# microcontroller.net
KiCad netlist of a schematic drawn in Altium Designer
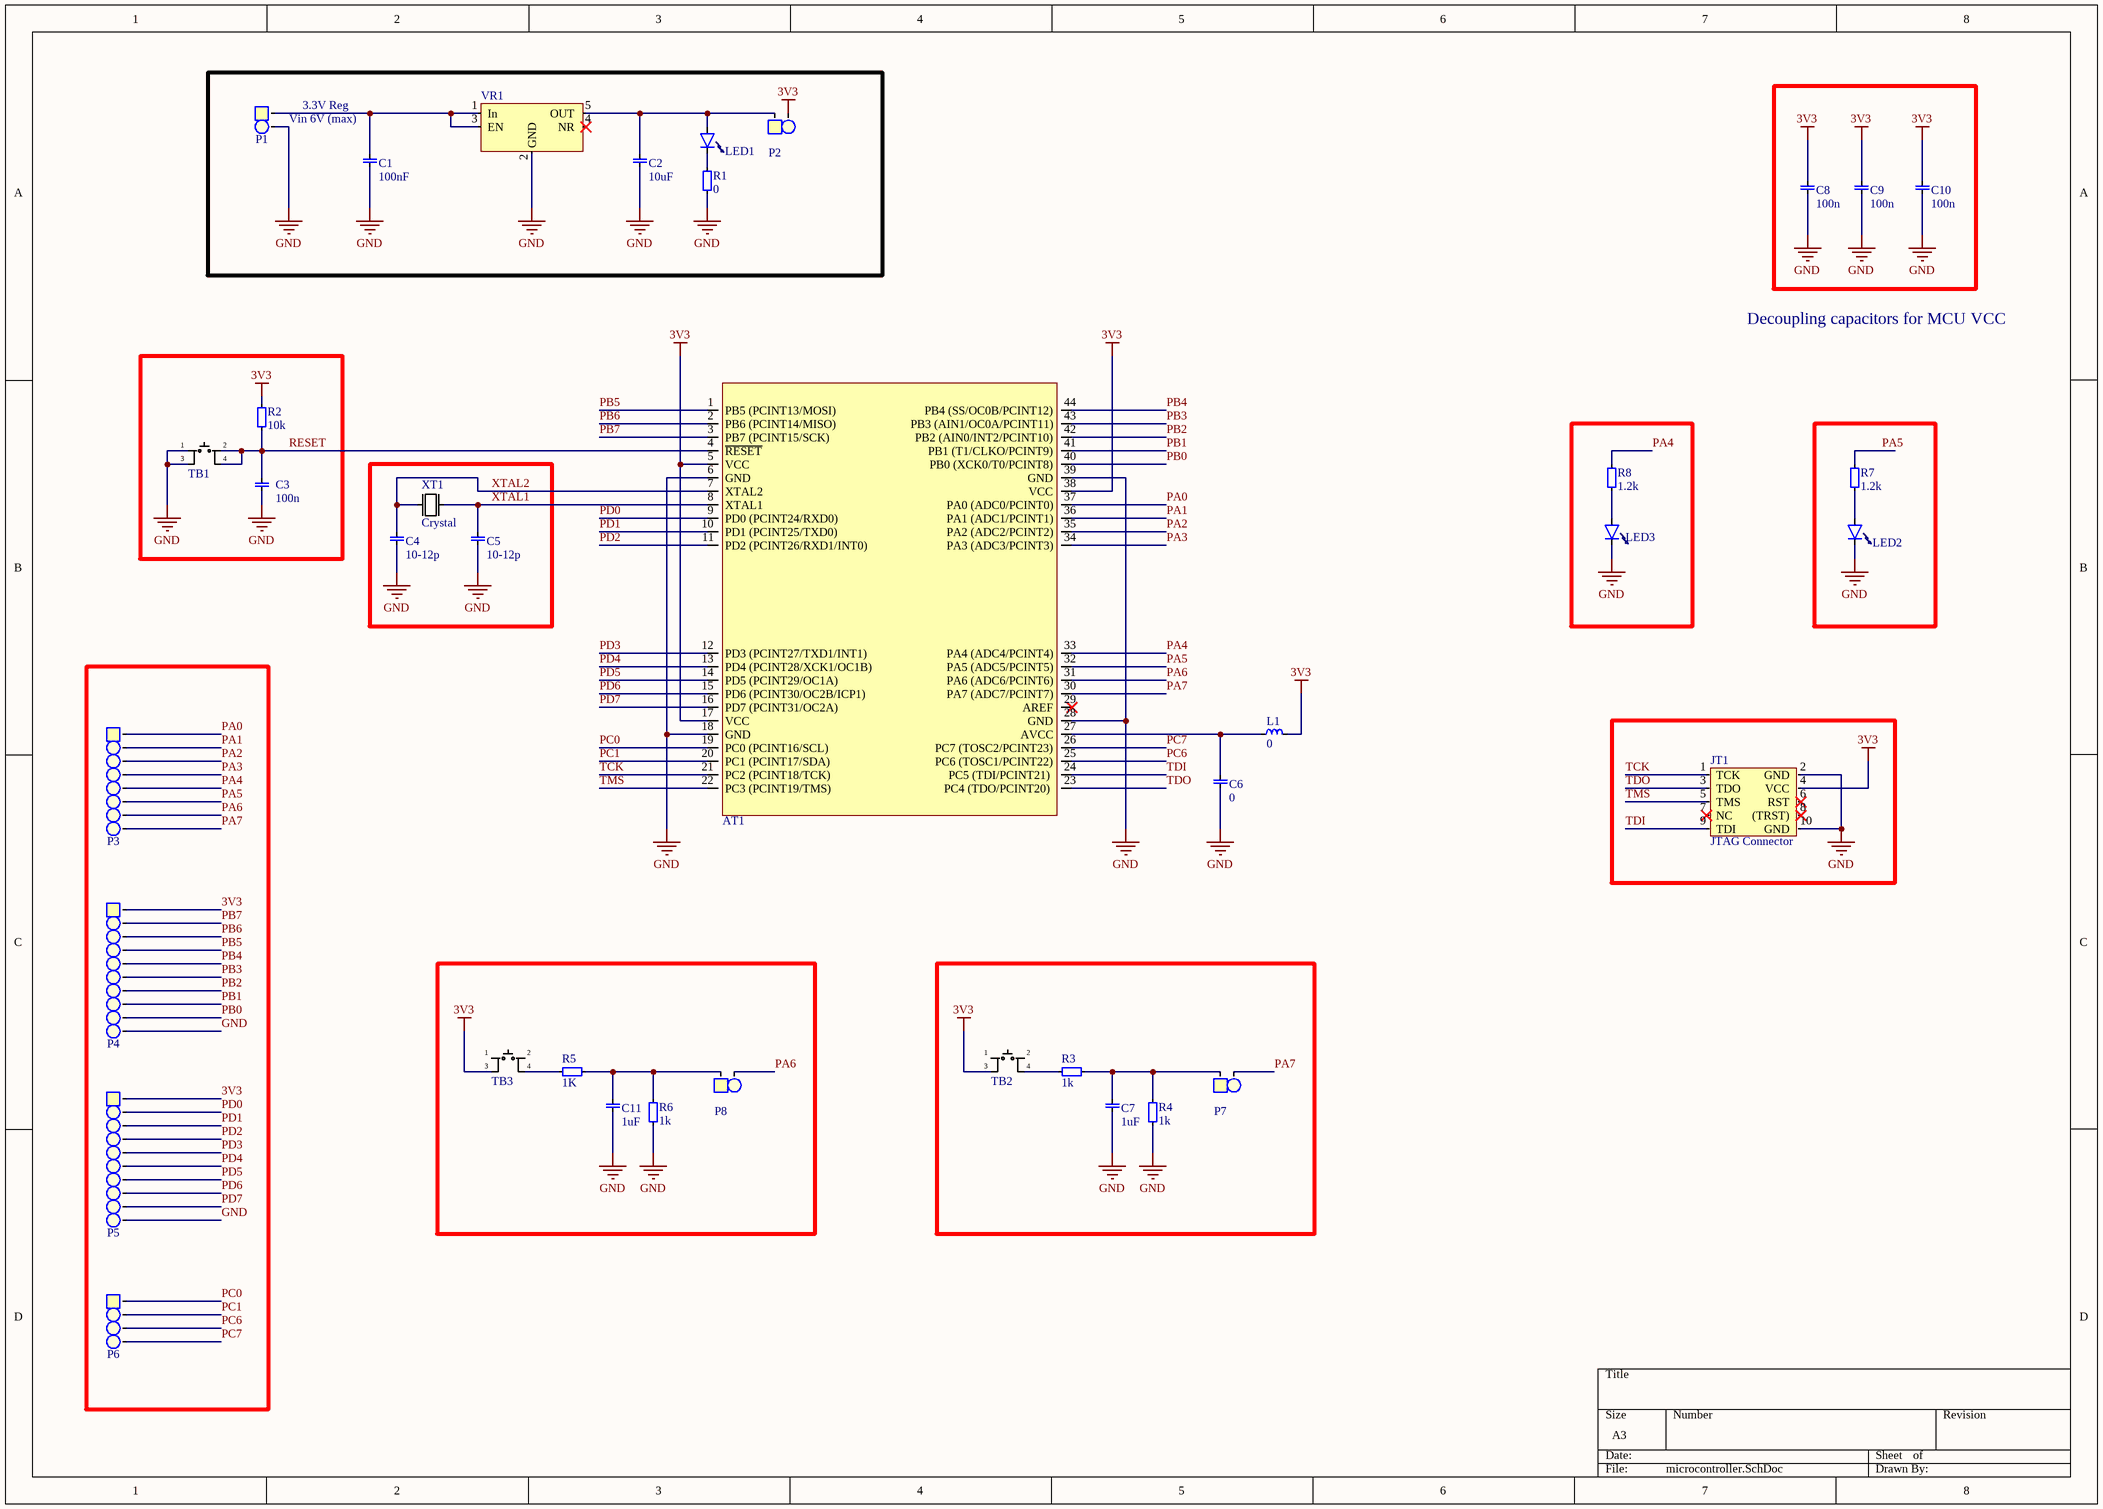
[diagram p0: microcontroller.SchDoc]

(export (version "E")
  (design (tool "Eeschema 10.0.6"))
  (components
    (comp (ref "AT1")
      (value "ATmega644PA")
      (footprint "TQFP-44")
      (description "ATmega644PA - Small but big and PicoPower")
      (libsource (lib "eitp15_lab1_lib") (part "ATmega644PA"))
    )
    (comp (ref "C1")
      (value "100nF")
      (footprint "1206, capasitor")
      (fields (field (name "Comment") "1206, capacitor"))
      (libsource (lib "eitp15_lab1_lib") (part "1206, capacitor"))
    )
    (comp (ref "C2")
      (value "10uF")
      (footprint "1206, capasitor")
      (fields (field (name "Comment") "1206, capacitor"))
      (libsource (lib "eitp15_lab1_lib") (part "1206, capacitor"))
    )
    (comp (ref "C3")
      (value "100n")
      (footprint "1206, capasitor")
      (fields (field (name "Comment") "1206, capacitor"))
      (libsource (lib "eitp15_lab1_lib") (part "1206, capacitor"))
    )
    (comp (ref "C4")
      (value "10-12p")
      (footprint "1206, capasitor")
      (fields (field (name "Comment") "1206, capacitor"))
      (libsource (lib "eitp15_lab1_lib") (part "1206, capacitor"))
    )
    (comp (ref "C5")
      (value "10-12p")
      (footprint "1206, capasitor")
      (fields (field (name "Comment") "1206, capacitor"))
      (libsource (lib "eitp15_lab1_lib") (part "1206, capacitor"))
    )
    (comp (ref "C6")
      (value "0")
      (footprint "1206, capasitor")
      (fields (field (name "Comment") "1206, capacitor"))
      (libsource (lib "eitp15_lab1_lib") (part "1206, capacitor"))
    )
    (comp (ref "C7")
      (value "1uF")
      (footprint "1206, capasitor")
      (fields (field (name "Comment") "1206, capacitor"))
      (libsource (lib "eitp15_lab1_lib") (part "1206, capacitor"))
    )
    (comp (ref "C8")
      (value "100n")
      (footprint "1206, capasitor")
      (fields (field (name "Comment") "1206, capacitor"))
      (libsource (lib "eitp15_lab1_lib") (part "1206, capacitor"))
    )
    (comp (ref "C9")
      (value "100n")
      (footprint "1206, capasitor")
      (fields (field (name "Comment") "1206, capacitor"))
      (libsource (lib "eitp15_lab1_lib") (part "1206, capacitor"))
    )
    (comp (ref "C10")
      (value "100n")
      (footprint "1206, capasitor")
      (fields (field (name "Comment") "1206, capacitor"))
      (libsource (lib "eitp15_lab1_lib") (part "1206, capacitor"))
    )
    (comp (ref "C11")
      (value "1uF")
      (footprint "1206, capasitor")
      (fields (field (name "Comment") "1206, capacitor"))
      (libsource (lib "eitp15_lab1_lib") (part "1206, capacitor"))
    )
    (comp (ref "JT1")
      (value "JTAG Connector")
      (footprint "Atmel_JTAG")
      (description "Atmel JTAG Connector")
      (libsource (lib "eitp15_lab1_lib") (part "Atmel JTAG"))
    )
    (comp (ref "L1")
      (value "0")
      (footprint "1812, coil")
      (fields (field (name "Comment") "Coil"))
      (libsource (lib "eitp15_lab1_lib") (part "Coil"))
    )
    (comp (ref "LED1")
      (value "0805, LED")
      (footprint "0805_led")
      (libsource (lib "eitp15_lab1_lib") (part "0805, LED"))
    )
    (comp (ref "LED2")
      (value "0805, LED")
      (footprint "0805_led")
      (libsource (lib "eitp15_lab1_lib") (part "0805, LED"))
    )
    (comp (ref "LED3")
      (value "0805, LED")
      (footprint "0805_led")
      (libsource (lib "eitp15_lab1_lib") (part "0805, LED"))
    )
    (comp (ref "P1")
      (value "1x2 Pin Header")
      (footprint "1x2HEADER")
      (description "2.54 mm, TH")
      (libsource (lib "") (part "1x2 Pin Header_1"))
    )
    (comp (ref "P2")
      (value "1x2 Pin Header")
      (footprint "1x2HEADER")
      (description "2.54 mm, TH")
      (libsource (lib "eitp15_lab1_lib") (part "1x2 Pin Header"))
    )
    (comp (ref "P3")
      (value "1x8 Pin Header")
      (footprint "1x8HEADER")
      (description "2.54 mm, TH")
      (libsource (lib "eitp15_lab1_lib") (part "1x8 Pin Header"))
    )
    (comp (ref "P4")
      (value "1x10 Pin Header")
      (footprint "1x10HEADER")
      (description "2.54 mm, TH")
      (libsource (lib "eitp15_lab1_lib") (part "1x10 Pin Header"))
    )
    (comp (ref "P5")
      (value "1x10 Pin Header")
      (footprint "1x10HEADER")
      (description "2.54 mm, TH")
      (libsource (lib "eitp15_lab1_lib") (part "1x10 Pin Header"))
    )
    (comp (ref "P6")
      (value "1x4 Pin Header")
      (footprint "1x4HEADER")
      (description "2.54 mm, TH")
      (libsource (lib "eitp15_lab1_lib") (part "1x4 Pin Header"))
    )
    (comp (ref "P7")
      (value "1x2 Pin Header")
      (footprint "1x2HEADER")
      (description "2.54 mm, TH")
      (libsource (lib "eitp15_lab1_lib") (part "1x2 Pin Header"))
    )
    (comp (ref "P8")
      (value "1x2 Pin Header")
      (footprint "1x2HEADER")
      (description "2.54 mm, TH")
      (libsource (lib "eitp15_lab1_lib") (part "1x2 Pin Header"))
    )
    (comp (ref "R1")
      (value "0")
      (footprint "1206")
      (description "Resistor")
      (fields (field (name "Comment") "1206, resistor"))
      (libsource (lib "eitp15_lab1_lib") (part "1206, resistor"))
    )
    (comp (ref "R2")
      (value "10k")
      (footprint "1206")
      (description "Resistor")
      (fields (field (name "Comment") "1206, resistor"))
      (libsource (lib "eitp15_lab1_lib") (part "1206, resistor"))
    )
    (comp (ref "R3")
      (value "1k")
      (footprint "1206")
      (description "Resistor")
      (fields (field (name "Comment") "1206, resistor"))
      (libsource (lib "eitp15_lab1_lib") (part "1206, resistor"))
    )
    (comp (ref "R4")
      (value "1k")
      (footprint "1206")
      (description "Resistor")
      (fields (field (name "Comment") "1206, resistor"))
      (libsource (lib "eitp15_lab1_lib") (part "1206, resistor"))
    )
    (comp (ref "R5")
      (value "1K")
      (footprint "1206")
      (description "Resistor")
      (fields (field (name "Comment") "1206, resistor"))
      (libsource (lib "eitp15_lab1_lib") (part "1206, resistor"))
    )
    (comp (ref "R6")
      (value "1k")
      (footprint "1206")
      (description "Resistor")
      (fields (field (name "Comment") "1206, resistor"))
      (libsource (lib "eitp15_lab1_lib") (part "1206, resistor"))
    )
    (comp (ref "R7")
      (value "1.2k")
      (footprint "1206")
      (description "Resistor")
      (fields (field (name "Comment") "1206, resistor"))
      (libsource (lib "eitp15_lab1_lib") (part "1206, resistor"))
    )
    (comp (ref "R8")
      (value "1.2k")
      (footprint "1206")
      (description "Resistor")
      (fields (field (name "Comment") "1206, resistor"))
      (libsource (lib "eitp15_lab1_lib") (part "1206, resistor"))
    )
    (comp (ref "TB1")
      (value "Tactile Button")
      (footprint "Button smd")
      (description "Tactile Switch Small Low")
      (libsource (lib "eitp15_lab1_lib") (part "Button SMD"))
    )
    (comp (ref "TB2")
      (value "Tactile Button")
      (footprint "Button smd")
      (description "Tactile Switch Small Low")
      (libsource (lib "eitp15_lab1_lib") (part "Button SMD"))
    )
    (comp (ref "TB3")
      (value "Tactile Button")
      (footprint "Button smd")
      (description "Tactile Switch Small Low")
      (libsource (lib "eitp15_lab1_lib") (part "Button SMD"))
    )
    (comp (ref "VR1")
      (value "3.3V Reg")
      (footprint "SOT23-5")
      (description "3.3V Reg, Ultra-Low Noise, 200 mA")
      (fields (field (name "INPUT VOLTAGE") "Vin 6V (max)"))
      (libsource (lib "eitp15_lab1_lib") (part "TPS79333DBR"))
    )
    (comp (ref "XT1")
      (value "Crystal")
      (footprint "XTAL_SMD_LP")
      (description "16 MHz, SMD, 5mm x 3,2mm, 30 ppm")
      (fields (field (name "Comment") "XTAL TXC 7A"))
      (libsource (lib "eitp15_lab1_lib") (part "XTAL TXC 7A"))
    )
  )
  (nets
    (net (code "1") (name "/PA0") (class "Default")
      (node (ref "AT1") (pin "37") (pinfunction "PA0_(ADC0/PCINT0)_37") (pintype "passive"))
      (node (ref "P3") (pin "1") (pinfunction "1_1") (pintype "passive"))
    )
    (net (code "2") (name "/PA1") (class "Default")
      (node (ref "AT1") (pin "36") (pinfunction "PA1_(ADC1/PCINT1)_36") (pintype "passive"))
      (node (ref "P3") (pin "2") (pinfunction "2_2") (pintype "passive"))
    )
    (net (code "3") (name "/PA2") (class "Default")
      (node (ref "AT1") (pin "35") (pinfunction "PA2_(ADC2/PCINT2)_35") (pintype "passive"))
      (node (ref "P3") (pin "3") (pinfunction "3_3") (pintype "passive"))
    )
    (net (code "4") (name "/PA3") (class "Default")
      (node (ref "AT1") (pin "34") (pinfunction "PA3_(ADC3/PCINT3)_34") (pintype "passive"))
      (node (ref "P3") (pin "4") (pinfunction "4_4") (pintype "passive"))
    )
    (net (code "5") (name "/PA4") (class "Default")
      (node (ref "AT1") (pin "33") (pinfunction "PA4_(ADC4/PCINT4)_33") (pintype "passive"))
      (node (ref "P3") (pin "5") (pinfunction "5_5") (pintype "passive"))
      (node (ref "R8") (pin "0") (pinfunction "0_0") (pintype "passive"))
    )
    (net (code "6") (name "/PA5") (class "Default")
      (node (ref "AT1") (pin "32") (pinfunction "PA5_(ADC5/PCINT5)_32") (pintype "passive"))
      (node (ref "P3") (pin "6") (pinfunction "6_6") (pintype "passive"))
      (node (ref "R7") (pin "0") (pinfunction "0_0") (pintype "passive"))
    )
    (net (code "7") (name "/PA6") (class "Default")
      (node (ref "AT1") (pin "31") (pinfunction "PA6_(ADC6/PCINT6)_31") (pintype "passive"))
      (node (ref "P3") (pin "7") (pinfunction "7_7") (pintype "passive"))
      (node (ref "P8") (pin "2") (pinfunction "2_2") (pintype "passive"))
    )
    (net (code "8") (name "/PA7") (class "Default")
      (node (ref "AT1") (pin "30") (pinfunction "PA7_(ADC7/PCINT7)_30") (pintype "passive"))
      (node (ref "P3") (pin "8") (pinfunction "8_8") (pintype "passive"))
      (node (ref "P7") (pin "2") (pinfunction "2_2") (pintype "passive"))
    )
    (net (code "9") (name "/PB0") (class "Default")
      (node (ref "AT1") (pin "40") (pinfunction "PB0_(XCK0/T0/PCINT8)_40") (pintype "passive"))
      (node (ref "P4") (pin "9") (pinfunction "9_9") (pintype "passive"))
    )
    (net (code "10") (name "/PB1") (class "Default")
      (node (ref "AT1") (pin "41") (pinfunction "PB1_(T1/CLKO/PCINT9)_41") (pintype "passive"))
      (node (ref "P4") (pin "8") (pinfunction "8_8") (pintype "passive"))
    )
    (net (code "11") (name "/PB2") (class "Default")
      (node (ref "AT1") (pin "42") (pinfunction "PB2_(AIN0/INT2/PCINT10)_42") (pintype "passive"))
      (node (ref "P4") (pin "7") (pinfunction "7_7") (pintype "passive"))
    )
    (net (code "12") (name "/PB3") (class "Default")
      (node (ref "AT1") (pin "43") (pinfunction "PB3_(AIN1/OC0A/PCINT11)_43") (pintype "passive"))
      (node (ref "P4") (pin "6") (pinfunction "6_6") (pintype "passive"))
    )
    (net (code "13") (name "/PB4") (class "Default")
      (node (ref "AT1") (pin "44") (pinfunction "PB4_(SS/OC0B/PCINT12)_44") (pintype "passive"))
      (node (ref "P4") (pin "5") (pinfunction "5_5") (pintype "passive"))
    )
    (net (code "14") (name "/PB5") (class "Default")
      (node (ref "AT1") (pin "1") (pinfunction "PB5_(PCINT13/MOSI)_1") (pintype "passive"))
      (node (ref "P4") (pin "4") (pinfunction "4_4") (pintype "passive"))
    )
    (net (code "15") (name "/PB6") (class "Default")
      (node (ref "AT1") (pin "2") (pinfunction "PB6_(PCINT14/MISO)_2") (pintype "passive"))
      (node (ref "P4") (pin "3") (pinfunction "3_3") (pintype "passive"))
    )
    (net (code "16") (name "/PB7") (class "Default")
      (node (ref "AT1") (pin "3") (pinfunction "PB7_(PCINT15/SCK)_3") (pintype "passive"))
      (node (ref "P4") (pin "2") (pinfunction "2_2") (pintype "passive"))
    )
    (net (code "17") (name "/PC0") (class "Default")
      (node (ref "AT1") (pin "19") (pinfunction "PC0_(PCINT16/SCL)_19") (pintype "passive"))
      (node (ref "P6") (pin "1") (pinfunction "1_1") (pintype "passive"))
    )
    (net (code "18") (name "/PC1") (class "Default")
      (node (ref "AT1") (pin "20") (pinfunction "PC1_(PCINT17/SDA)_20") (pintype "passive"))
      (node (ref "P6") (pin "2") (pinfunction "2_2") (pintype "passive"))
    )
    (net (code "19") (name "/PC6") (class "Default")
      (node (ref "AT1") (pin "25") (pinfunction "PC6_(TOSC1/PCINT22)_25") (pintype "passive"))
      (node (ref "P6") (pin "3") (pinfunction "3_3") (pintype "passive"))
    )
    (net (code "20") (name "/PC7") (class "Default")
      (node (ref "AT1") (pin "26") (pinfunction "PC7_(TOSC2/PCINT23)_26") (pintype "passive"))
      (node (ref "P6") (pin "4") (pinfunction "4_4") (pintype "passive"))
    )
    (net (code "21") (name "/PD0") (class "Default")
      (node (ref "AT1") (pin "9") (pinfunction "PD0_(PCINT24/RXD0)_9") (pintype "passive"))
      (node (ref "P5") (pin "2") (pinfunction "2_2") (pintype "passive"))
    )
    (net (code "22") (name "/PD1") (class "Default")
      (node (ref "AT1") (pin "10") (pinfunction "PD1_(PCINT25/TXD0)_10") (pintype "passive"))
      (node (ref "P5") (pin "3") (pinfunction "3_3") (pintype "passive"))
    )
    (net (code "23") (name "/PD2") (class "Default")
      (node (ref "AT1") (pin "11") (pinfunction "PD2_(PCINT26/RXD1/INT0)_11") (pintype "passive"))
      (node (ref "P5") (pin "4") (pinfunction "4_4") (pintype "passive"))
    )
    (net (code "24") (name "/PD3") (class "Default")
      (node (ref "AT1") (pin "12") (pinfunction "PD3_(PCINT27/TXD1/INT1)_12") (pintype "passive"))
      (node (ref "P5") (pin "5") (pinfunction "5_5") (pintype "passive"))
    )
    (net (code "25") (name "/PD4") (class "Default")
      (node (ref "AT1") (pin "13") (pinfunction "PD4_(PCINT28/XCK1/OC1B)_13") (pintype "passive"))
      (node (ref "P5") (pin "6") (pinfunction "6_6") (pintype "passive"))
    )
    (net (code "26") (name "/PD5") (class "Default")
      (node (ref "AT1") (pin "14") (pinfunction "PD5_(PCINT29/OC1A)_14") (pintype "passive"))
      (node (ref "P5") (pin "7") (pinfunction "7_7") (pintype "passive"))
    )
    (net (code "27") (name "/PD6") (class "Default")
      (node (ref "AT1") (pin "15") (pinfunction "PD6_(PCINT30/OC2B/ICP1)_15") (pintype "passive"))
      (node (ref "P5") (pin "8") (pinfunction "8_8") (pintype "passive"))
    )
    (net (code "28") (name "/PD7") (class "Default")
      (node (ref "AT1") (pin "16") (pinfunction "PD7_(PCINT31/OC2A)_16") (pintype "passive"))
      (node (ref "P5") (pin "9") (pinfunction "9_9") (pintype "passive"))
    )
    (net (code "29") (name "/RESET") (class "Default")
      (node (ref "AT1") (pin "4") (pinfunction "~{RESET}_4") (pintype "passive"))
      (node (ref "C3") (pin "1") (pinfunction "1_1") (pintype "passive"))
      (node (ref "R2") (pin "1") (pinfunction "1_1") (pintype "passive"))
      (node (ref "TB1") (pin "2") (pinfunction "2_2") (pintype "passive"))
      (node (ref "TB1") (pin "4") (pinfunction "4_4") (pintype "passive"))
    )
    (net (code "30") (name "/TCK") (class "Default")
      (node (ref "AT1") (pin "21") (pinfunction "PC2_(PCINT18/TCK)_21") (pintype "passive"))
      (node (ref "JT1") (pin "1") (pinfunction "TCK_1") (pintype "passive"))
    )
    (net (code "31") (name "/TDI") (class "Default")
      (node (ref "AT1") (pin "24") (pinfunction "PC5_(TDI/PCINT21)_24") (pintype "passive"))
      (node (ref "JT1") (pin "9") (pinfunction "TDI_9") (pintype "passive"))
    )
    (net (code "32") (name "/TDO") (class "Default")
      (node (ref "AT1") (pin "23") (pinfunction "PC4_(TDO/PCINT20)_23") (pintype "passive"))
      (node (ref "JT1") (pin "3") (pinfunction "TDO_3") (pintype "passive"))
    )
    (net (code "33") (name "/TMS") (class "Default")
      (node (ref "AT1") (pin "22") (pinfunction "PC3_(PCINT19/TMS)_22") (pintype "passive"))
      (node (ref "JT1") (pin "5") (pinfunction "TMS_5") (pintype "passive"))
    )
    (net (code "34") (name "/XTAL1") (class "Default")
      (node (ref "AT1") (pin "8") (pinfunction "XTAL1_8") (pintype "passive"))
      (node (ref "C5") (pin "1") (pinfunction "1_1") (pintype "passive"))
      (node (ref "XT1") (pin "2") (pinfunction "2_2") (pintype "passive"))
    )
    (net (code "35") (name "/XTAL2") (class "Default")
      (node (ref "AT1") (pin "7") (pinfunction "XTAL2_7") (pintype "passive"))
      (node (ref "C4") (pin "1") (pinfunction "1_1") (pintype "passive"))
      (node (ref "XT1") (pin "1") (pinfunction "1_1") (pintype "passive"))
    )
    (net (code "36") (name "3V3") (class "Default")
      (node (ref "AT1") (pin "17") (pinfunction "VCC_17") (pintype "passive"))
      (node (ref "AT1") (pin "38") (pinfunction "VCC_38") (pintype "passive"))
      (node (ref "AT1") (pin "5") (pinfunction "VCC_5") (pintype "passive"))
      (node (ref "C10") (pin "1") (pinfunction "1_1") (pintype "passive"))
      (node (ref "C8") (pin "1") (pinfunction "1_1") (pintype "passive"))
      (node (ref "C9") (pin "1") (pinfunction "1_1") (pintype "passive"))
      (node (ref "JT1") (pin "4") (pinfunction "VCC_4") (pintype "passive"))
      (node (ref "L1") (pin "1") (pinfunction "1_1") (pintype "passive"))
      (node (ref "P2") (pin "2") (pinfunction "2_2") (pintype "passive"))
      (node (ref "P4") (pin "1") (pinfunction "1_1") (pintype "passive"))
      (node (ref "P5") (pin "1") (pinfunction "1_1") (pintype "passive"))
      (node (ref "R2") (pin "0") (pinfunction "0_0") (pintype "passive"))
      (node (ref "TB2") (pin "3") (pinfunction "3_3") (pintype "passive"))
      (node (ref "TB3") (pin "3") (pinfunction "3_3") (pintype "passive"))
    )
    (net (code "37") (name "GND") (class "Default")
      (node (ref "AT1") (pin "18") (pinfunction "GND_18") (pintype "passive"))
      (node (ref "AT1") (pin "28") (pinfunction "GND_28") (pintype "passive"))
      (node (ref "AT1") (pin "39") (pinfunction "GND_39") (pintype "passive"))
      (node (ref "AT1") (pin "6") (pinfunction "GND_6") (pintype "passive"))
      (node (ref "C1") (pin "1") (pinfunction "1_1") (pintype "passive"))
      (node (ref "C10") (pin "0") (pinfunction "0_0") (pintype "passive"))
      (node (ref "C11") (pin "0") (pinfunction "0_0") (pintype "passive"))
      (node (ref "C2") (pin "1") (pinfunction "1_1") (pintype "passive"))
      (node (ref "C3") (pin "0") (pinfunction "0_0") (pintype "passive"))
      (node (ref "C4") (pin "0") (pinfunction "0_0") (pintype "passive"))
      (node (ref "C5") (pin "0") (pinfunction "0_0") (pintype "passive"))
      (node (ref "C6") (pin "0") (pinfunction "0_0") (pintype "passive"))
      (node (ref "C7") (pin "0") (pinfunction "0_0") (pintype "passive"))
      (node (ref "C8") (pin "0") (pinfunction "0_0") (pintype "passive"))
      (node (ref "C9") (pin "0") (pinfunction "0_0") (pintype "passive"))
      (node (ref "JT1") (pin "10") (pinfunction "GND_10") (pintype "passive"))
      (node (ref "JT1") (pin "2") (pinfunction "GND_2") (pintype "passive"))
      (node (ref "LED2") (pin "0") (pinfunction "Cathode_0") (pintype "passive"))
      (node (ref "LED3") (pin "0") (pinfunction "Cathode_0") (pintype "passive"))
      (node (ref "P1") (pin "2") (pinfunction "2_2") (pintype "passive"))
      (node (ref "P4") (pin "10") (pinfunction "10_10") (pintype "passive"))
      (node (ref "P5") (pin "10") (pinfunction "10_10") (pintype "passive"))
      (node (ref "R1") (pin "1") (pinfunction "1_1") (pintype "passive"))
      (node (ref "R4") (pin "1") (pinfunction "1_1") (pintype "passive"))
      (node (ref "R6") (pin "1") (pinfunction "1_1") (pintype "passive"))
      (node (ref "TB1") (pin "1") (pinfunction "1_1") (pintype "passive"))
      (node (ref "TB1") (pin "3") (pinfunction "3_3") (pintype "passive"))
      (node (ref "VR1") (pin "2") (pinfunction "GND_2") (pintype "passive"))
    )
    (net (code "38") (name "Net-(AT1-AVCC)") (class "Default")
      (node (ref "AT1") (pin "27") (pinfunction "AVCC_27") (pintype "passive"))
      (node (ref "C6") (pin "1") (pinfunction "1_1") (pintype "passive"))
      (node (ref "L1") (pin "2") (pinfunction "2_2") (pintype "passive"))
    )
    (net (code "39") (name "Net-(C7-Pad1)") (class "Default")
      (node (ref "C7") (pin "1") (pinfunction "1_1") (pintype "passive"))
      (node (ref "P7") (pin "1") (pinfunction "1_1") (pintype "passive"))
      (node (ref "R3") (pin "0") (pinfunction "0_0") (pintype "passive"))
      (node (ref "R4") (pin "0") (pinfunction "0_0") (pintype "passive"))
    )
    (net (code "40") (name "Net-(C11-Pad1)") (class "Default")
      (node (ref "C11") (pin "1") (pinfunction "1_1") (pintype "passive"))
      (node (ref "P8") (pin "1") (pinfunction "1_1") (pintype "passive"))
      (node (ref "R5") (pin "0") (pinfunction "0_0") (pintype "passive"))
      (node (ref "R6") (pin "0") (pinfunction "0_0") (pintype "passive"))
    )
    (net (code "41") (name "Net-(LED1-Cathode)") (class "Default")
      (node (ref "LED1") (pin "0") (pinfunction "Cathode_0") (pintype "passive"))
      (node (ref "R1") (pin "0") (pinfunction "0_0") (pintype "passive"))
    )
    (net (code "42") (name "Net-(LED2-Pad1)") (class "Default")
      (node (ref "LED2") (pin "1") (pinfunction "1_1") (pintype "passive"))
      (node (ref "R7") (pin "1") (pinfunction "1_1") (pintype "passive"))
    )
    (net (code "43") (name "Net-(LED3-Pad1)") (class "Default")
      (node (ref "LED3") (pin "1") (pinfunction "1_1") (pintype "passive"))
      (node (ref "R8") (pin "1") (pinfunction "1_1") (pintype "passive"))
    )
    (net (code "44") (name "Net-(R3-Pad1)") (class "Default")
      (node (ref "R3") (pin "1") (pinfunction "1_1") (pintype "passive"))
      (node (ref "TB2") (pin "4") (pinfunction "4_4") (pintype "passive"))
    )
    (net (code "45") (name "Net-(R5-Pad1)") (class "Default")
      (node (ref "R5") (pin "1") (pinfunction "1_1") (pintype "passive"))
      (node (ref "TB3") (pin "4") (pinfunction "4_4") (pintype "passive"))
    )
    (net (code "46") (name "Net-(VR1-EN)") (class "Default")
      (node (ref "C1") (pin "0") (pinfunction "0_0") (pintype "passive"))
      (node (ref "P1") (pin "1") (pinfunction "1_1") (pintype "passive"))
      (node (ref "VR1") (pin "1") (pinfunction "In_1") (pintype "passive"))
      (node (ref "VR1") (pin "3") (pinfunction "EN_3") (pintype "passive"))
    )
    (net (code "47") (name "Net-(VR1-OUT)") (class "Default")
      (node (ref "C2") (pin "0") (pinfunction "0_0") (pintype "passive"))
      (node (ref "LED1") (pin "1") (pinfunction "1_1") (pintype "passive"))
      (node (ref "P2") (pin "1") (pinfunction "1_1") (pintype "passive"))
      (node (ref "VR1") (pin "5") (pinfunction "OUT_5") (pintype "passive"))
    )
    (net (code "48") (name "unconnected-(AT1-AREF-Pad29)") (class "Default")
      (node (ref "AT1") (pin "29") (pinfunction "AREF_29") (pintype "passive+no_connect"))
    )
    (net (code "49") (name "unconnected-(JT1-(TRST)-Pad8)") (class "Default")
      (node (ref "JT1") (pin "8") (pinfunction "(TRST)_8") (pintype "passive+no_connect"))
    )
    (net (code "50") (name "unconnected-(JT1-NC-Pad7)") (class "Default")
      (node (ref "JT1") (pin "7") (pinfunction "NC_7") (pintype "passive+no_connect"))
    )
    (net (code "51") (name "unconnected-(JT1-RST-Pad6)") (class "Default")
      (node (ref "JT1") (pin "6") (pinfunction "RST_6") (pintype "passive+no_connect"))
    )
    (net (code "52") (name "unconnected-(TB2-Pad1)") (class "Default")
      (node (ref "TB2") (pin "1") (pinfunction "1_1") (pintype "passive"))
    )
    (net (code "53") (name "unconnected-(TB2-Pad2)") (class "Default")
      (node (ref "TB2") (pin "2") (pinfunction "2_2") (pintype "passive"))
    )
    (net (code "54") (name "unconnected-(TB3-Pad1)") (class "Default")
      (node (ref "TB3") (pin "1") (pinfunction "1_1") (pintype "passive"))
    )
    (net (code "55") (name "unconnected-(TB3-Pad2)") (class "Default")
      (node (ref "TB3") (pin "2") (pinfunction "2_2") (pintype "passive"))
    )
    (net (code "56") (name "unconnected-(VR1-NR-Pad4)") (class "Default")
      (node (ref "VR1") (pin "4") (pinfunction "NR_4") (pintype "passive+no_connect"))
    )
  )
)
